# memory.net
KiCad netlist of a schematic drawn in Altium Designer
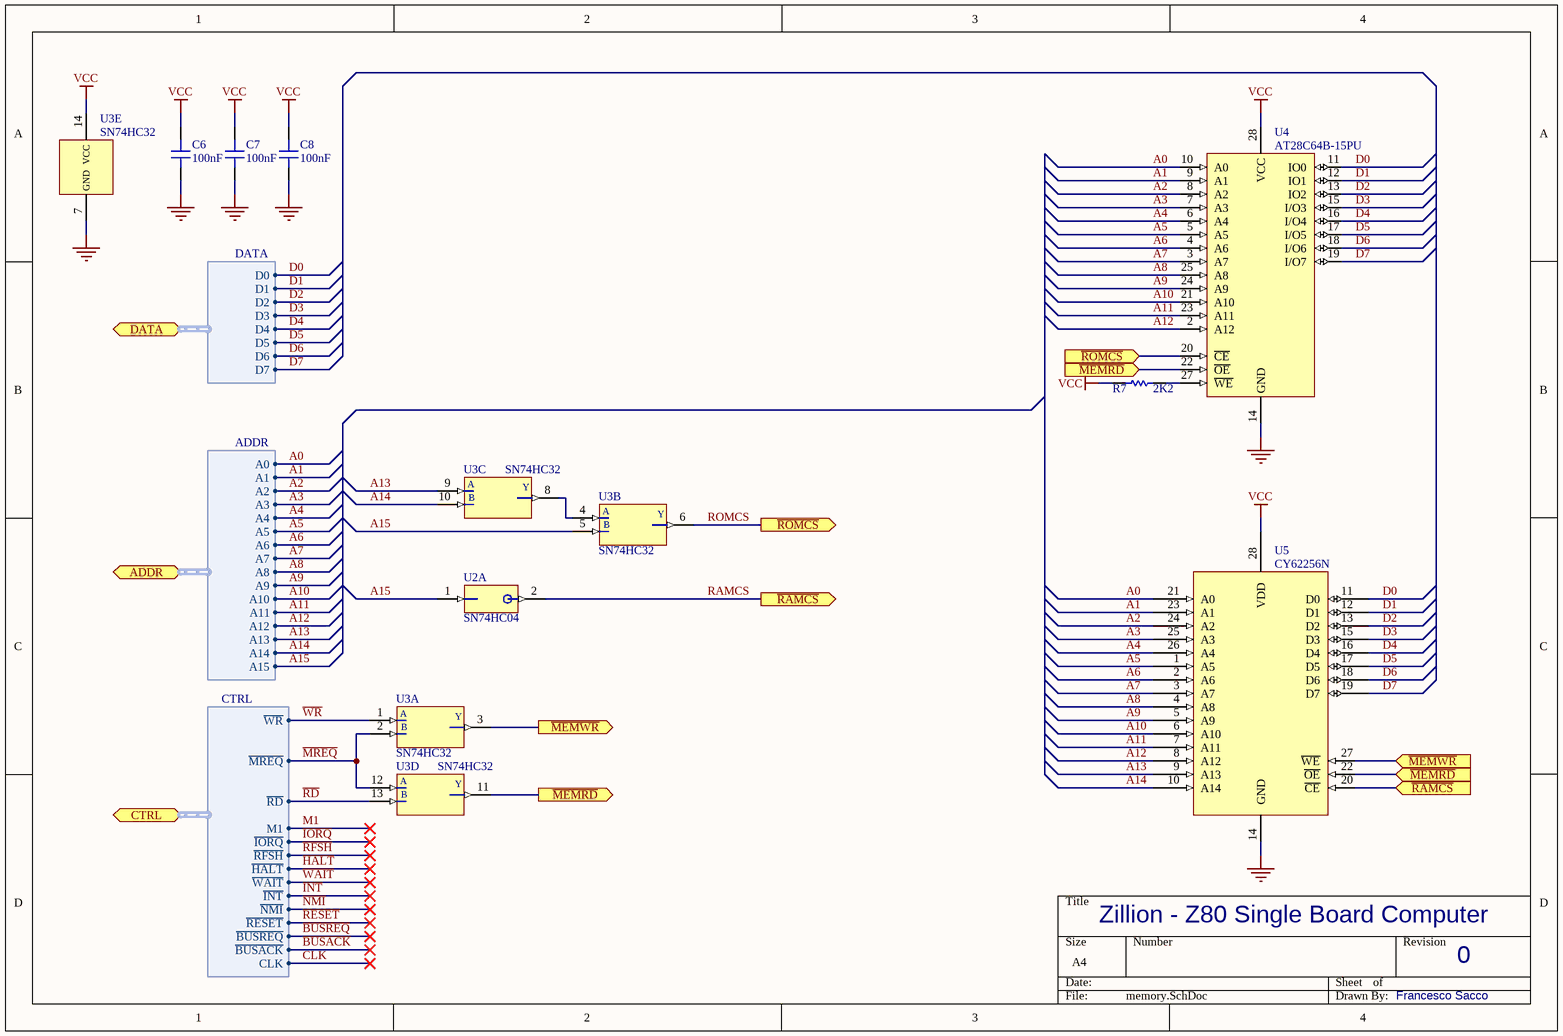
[diagram p0: memory.SchDoc]

(export (version "E")
  (design (tool "Eeschema 10.0.6"))
  (components
    (comp (ref "C6")
      (value "100nF")
      (footprint "DiskCapacitor")
      (description "Capacitor")
      (libsource (lib "Basic") (part "Capacitor"))
    )
    (comp (ref "C7")
      (value "100nF")
      (footprint "DiskCapacitor")
      (description "Capacitor")
      (libsource (lib "Basic") (part "Capacitor"))
    )
    (comp (ref "C8")
      (value "100nF")
      (footprint "DiskCapacitor")
      (description "Capacitor")
      (libsource (lib "Basic") (part "Capacitor"))
    )
    (comp (ref "R7") (value "2K2") (footprint "CR12") (libsource (lib "Basic") (part "Resistor")))
    (comp (ref "U2")
      (value "SN74HC04")
      (footprint "CDIP14")
      (description "Hex Inverters")
      (libsource (lib "Texas Instruments") (part "SN74HC04"))
    )
    (comp (ref "U3")
      (value "SN74HC32")
      (footprint "CDIP14")
      (description "Quadruple 2-Input Positive-OR Gates")
      (libsource (lib "Texas Instruments") (part "SN74HC32"))
    )
    (comp (ref "U4")
      (value "AT28C64B-15PU")
      (footprint "PDIP28")
      (description "64K (8K x 8) Parallel EEPROM")
      (libsource (lib "Microchip") (part "AT28C64B-15PU"))
    )
    (comp (ref "U5")
      (value "CY62256N")
      (footprint "PDIP28")
      (description "256-Kbit (32 K × 8) Static RAM")
      (libsource (lib "Cypress") (part "CY62256N"))
    )
  )
  (nets
    (net (code "4") (name "/A0") (class "Default")
      (node (ref "U4") (pin "10") (pinfunction "A0_10") (pintype "input"))
      (node (ref "U5") (pin "21") (pinfunction "A0_21") (pintype "input"))
    )
    (net (code "5") (name "/A1") (class "Default")
      (node (ref "U4") (pin "9") (pinfunction "A1_9") (pintype "input"))
      (node (ref "U5") (pin "23") (pinfunction "A1_23") (pintype "input"))
    )
    (net (code "6") (name "/A2") (class "Default")
      (node (ref "U4") (pin "8") (pinfunction "A2_8") (pintype "input"))
      (node (ref "U5") (pin "24") (pinfunction "A2_24") (pintype "input"))
    )
    (net (code "7") (name "/A3") (class "Default")
      (node (ref "U4") (pin "7") (pinfunction "A3_7") (pintype "input"))
      (node (ref "U5") (pin "25") (pinfunction "A3_25") (pintype "input"))
    )
    (net (code "8") (name "/A4") (class "Default")
      (node (ref "U4") (pin "6") (pinfunction "A4_6") (pintype "input"))
      (node (ref "U5") (pin "26") (pinfunction "A4_26") (pintype "input"))
    )
    (net (code "9") (name "/A5") (class "Default")
      (node (ref "U4") (pin "5") (pinfunction "A5_5") (pintype "input"))
      (node (ref "U5") (pin "1") (pinfunction "A5_1") (pintype "input"))
    )
    (net (code "10") (name "/A6") (class "Default")
      (node (ref "U4") (pin "4") (pinfunction "A6_4") (pintype "input"))
      (node (ref "U5") (pin "2") (pinfunction "A6_2") (pintype "input"))
    )
    (net (code "11") (name "/A7") (class "Default")
      (node (ref "U4") (pin "3") (pinfunction "A7_3") (pintype "input"))
      (node (ref "U5") (pin "3") (pinfunction "A7_3") (pintype "input"))
    )
    (net (code "12") (name "/A8") (class "Default")
      (node (ref "U4") (pin "25") (pinfunction "A8_25") (pintype "input"))
      (node (ref "U5") (pin "4") (pinfunction "A8_4") (pintype "input"))
    )
    (net (code "13") (name "/A9") (class "Default")
      (node (ref "U4") (pin "24") (pinfunction "A9_24") (pintype "input"))
      (node (ref "U5") (pin "5") (pinfunction "A9_5") (pintype "input"))
    )
    (net (code "14") (name "/A10") (class "Default")
      (node (ref "U4") (pin "21") (pinfunction "A10_21") (pintype "input"))
      (node (ref "U5") (pin "6") (pinfunction "A10_6") (pintype "input"))
    )
    (net (code "15") (name "/A11") (class "Default")
      (node (ref "U4") (pin "23") (pinfunction "A11_23") (pintype "input"))
      (node (ref "U5") (pin "7") (pinfunction "A11_7") (pintype "input"))
    )
    (net (code "16") (name "/A12") (class "Default")
      (node (ref "U4") (pin "2") (pinfunction "A12_2") (pintype "input"))
      (node (ref "U5") (pin "8") (pinfunction "A12_8") (pintype "input"))
    )
    (net (code "17") (name "/A13") (class "Default")
      (node (ref "U3") (pin "9") (pinfunction "A_9") (pintype "input"))
      (node (ref "U5") (pin "9") (pinfunction "A13_9") (pintype "input"))
    )
    (net (code "18") (name "/A14") (class "Default")
      (node (ref "U3") (pin "10") (pinfunction "B_10") (pintype "input"))
      (node (ref "U5") (pin "10") (pinfunction "A14_10") (pintype "input"))
    )
    (net (code "19") (name "/A15") (class "Default")
      (node (ref "U2") (pin "1") (pinfunction "A_1") (pintype "input"))
      (node (ref "U3") (pin "5") (pinfunction "B_5") (pintype "input"))
    )
    (net (code "21") (name "/D0") (class "Default")
      (node (ref "U4") (pin "11") (pinfunction "IO0_11") (pintype "bidirectional"))
      (node (ref "U5") (pin "11") (pinfunction "D0_11") (pintype "bidirectional"))
    )
    (net (code "22") (name "/D1") (class "Default")
      (node (ref "U4") (pin "12") (pinfunction "IO1_12") (pintype "bidirectional"))
      (node (ref "U5") (pin "12") (pinfunction "D1_12") (pintype "bidirectional"))
    )
    (net (code "23") (name "/D2") (class "Default")
      (node (ref "U4") (pin "13") (pinfunction "IO2_13") (pintype "bidirectional"))
      (node (ref "U5") (pin "13") (pinfunction "D2_13") (pintype "bidirectional"))
    )
    (net (code "24") (name "/D3") (class "Default")
      (node (ref "U4") (pin "15") (pinfunction "I/O3_15") (pintype "bidirectional"))
      (node (ref "U5") (pin "15") (pinfunction "D3_15") (pintype "bidirectional"))
    )
    (net (code "25") (name "/D4") (class "Default")
      (node (ref "U4") (pin "16") (pinfunction "I/O4_16") (pintype "bidirectional"))
      (node (ref "U5") (pin "16") (pinfunction "D4_16") (pintype "bidirectional"))
    )
    (net (code "26") (name "/D5") (class "Default")
      (node (ref "U4") (pin "17") (pinfunction "I/O5_17") (pintype "bidirectional"))
      (node (ref "U5") (pin "17") (pinfunction "D5_17") (pintype "bidirectional"))
    )
    (net (code "27") (name "/D6") (class "Default")
      (node (ref "U4") (pin "18") (pinfunction "I/O6_18") (pintype "bidirectional"))
      (node (ref "U5") (pin "18") (pinfunction "D6_18") (pintype "bidirectional"))
    )
    (net (code "28") (name "/D7") (class "Default")
      (node (ref "U4") (pin "19") (pinfunction "I/O7_19") (pintype "bidirectional"))
      (node (ref "U5") (pin "19") (pinfunction "D7_19") (pintype "bidirectional"))
    )
    (net (code "30") (name "/RAMCS") (class "Default")
      (node (ref "U2") (pin "2") (pinfunction "Y_2") (pintype "output"))
      (node (ref "U5") (pin "20") (pinfunction "~{CE}_20") (pintype "input"))
    )
    (net (code "31") (name "/ROMCS") (class "Default")
      (node (ref "U3") (pin "6") (pinfunction "Y_6") (pintype "output"))
      (node (ref "U4") (pin "20") (pinfunction "~{CE}_20") (pintype "input"))
    )
    (net (code "40") (name "/~{MEMRD}") (class "Default")
      (node (ref "U3") (pin "11") (pinfunction "Y_11") (pintype "output"))
      (node (ref "U4") (pin "22") (pinfunction "~{OE}_22") (pintype "input"))
      (node (ref "U5") (pin "22") (pinfunction "~{OE}_22") (pintype "input"))
    )
    (net (code "41") (name "/~{MEMWR}") (class "Default")
      (node (ref "U3") (pin "3") (pinfunction "Y_3") (pintype "output"))
      (node (ref "U5") (pin "27") (pinfunction "~{WE}_27") (pintype "input"))
    )
    (net (code "42") (name "/~{MREQ}") (class "Default")
      (node (ref "U3") (pin "12") (pinfunction "A_12") (pintype "input"))
      (node (ref "U3") (pin "2") (pinfunction "B_2") (pintype "input"))
    )
    (net (code "44") (name "/~{RD}") (class "Default")
      (node (ref "U3") (pin "13") (pinfunction "B_13") (pintype "input"))
    )
    (net (code "48") (name "/~{WR}") (class "Default")
      (node (ref "U3") (pin "1") (pinfunction "A_1") (pintype "input"))
    )
    (net (code "49") (name "GND") (class "Default")
      (node (ref "C6") (pin "1") (pinfunction "1_1") (pintype "passive"))
      (node (ref "C7") (pin "1") (pinfunction "1_1") (pintype "passive"))
      (node (ref "C8") (pin "1") (pinfunction "1_1") (pintype "passive"))
      (node (ref "U3") (pin "7") (pinfunction "GND_7") (pintype "power_in"))
      (node (ref "U4") (pin "14") (pinfunction "GND_14") (pintype "power_in"))
      (node (ref "U5") (pin "14") (pinfunction "GND_14") (pintype "power_in"))
    )
    (net (code "50") (name "Net-(U3B-A)") (class "Default")
      (node (ref "U3") (pin "4") (pinfunction "A_4") (pintype "input"))
      (node (ref "U3") (pin "8") (pinfunction "Y_8") (pintype "output"))
    )
    (net (code "51") (name "Net-(U4-~{WE})") (class "Default")
      (node (ref "R7") (pin "1") (pinfunction "1_1") (pintype "passive"))
      (node (ref "U4") (pin "27") (pinfunction "~{WE}_27") (pintype "input"))
    )
    (net (code "52") (name "VCC") (class "Default")
      (node (ref "C6") (pin "2") (pinfunction "2_2") (pintype "passive"))
      (node (ref "C7") (pin "2") (pinfunction "2_2") (pintype "passive"))
      (node (ref "C8") (pin "2") (pinfunction "2_2") (pintype "passive"))
      (node (ref "R7") (pin "2") (pinfunction "2_2") (pintype "passive"))
      (node (ref "U3") (pin "14") (pinfunction "VCC_14") (pintype "power_in"))
      (node (ref "U4") (pin "28") (pinfunction "VCC_28") (pintype "power_in"))
      (node (ref "U5") (pin "28") (pinfunction "VDD_28") (pintype "power_in"))
    )
  )
)
